# EEPROM.net
KiCad netlist of a schematic drawn in Altium Designer
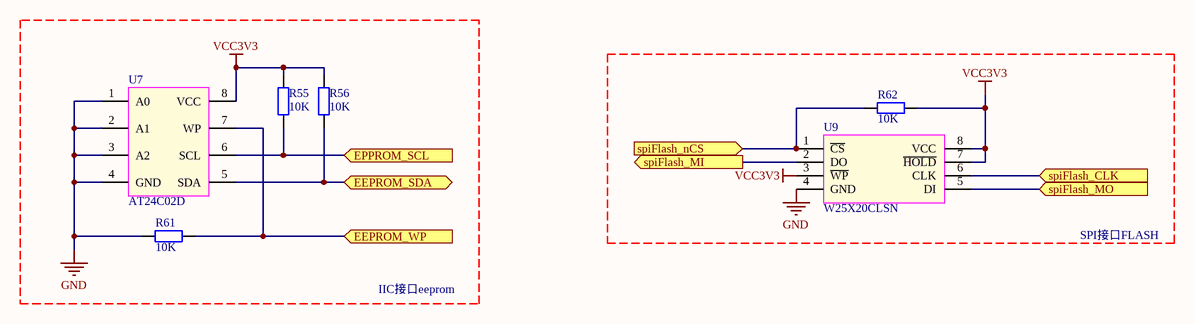
[diagram p0: EEPROM.SchDoc]

(export (version "E")
  (design (tool "Eeschema 10.0.6"))
  (components
    (comp (ref "R55")
      (value "10K")
      (footprint "R0603")
      (libsource (lib "altium-import") (part "root_3_RES_06_"))
    )
    (comp (ref "R56")
      (value "10K")
      (footprint "R0603")
      (libsource (lib "altium-import") (part "root_3_RES_06_"))
    )
    (comp (ref "R61")
      (value "10K")
      (footprint "R0603")
      (libsource (lib "altium-import") (part "root_0_RES_06_"))
    )
    (comp (ref "R62")
      (value "10K")
      (footprint "R0603")
      (libsource (lib "altium-import") (part "root_0_RES_06_"))
    )
    (comp (ref "U7")
      (value "AT24C02D")
      (footprint "SOP8")
      (description "EEPROM")
      (libsource (lib "MAX51") (part "AT24C02D"))
    )
    (comp (ref "U9")
      (value "W25X20CLSN")
      (footprint "SOP8")
      (description "2M-bit/256K Byte(262,144)")
      (libsource (lib "MAX51") (part "W25X20CLSN"))
    )
  )
  (nets
    (net (code "1") (name "/EEPROM_SDA") (class "Default")
      (node (ref "R56") (pin "2") (pinfunction "2_2") (pintype "passive"))
      (node (ref "U7") (pin "5") (pinfunction "SDA_5") (pintype "passive"))
    )
    (net (code "2") (name "/EEPROM_WP") (class "Default")
      (node (ref "R61") (pin "2") (pinfunction "2_2") (pintype "passive"))
      (node (ref "U7") (pin "7") (pinfunction "WP_7") (pintype "passive"))
    )
    (net (code "3") (name "/EPPROM_SCL") (class "Default")
      (node (ref "R55") (pin "2") (pinfunction "2_2") (pintype "passive"))
      (node (ref "U7") (pin "6") (pinfunction "SCL_6") (pintype "passive"))
    )
    (net (code "4") (name "/spiFlash_CLK") (class "Default")
      (node (ref "U9") (pin "6") (pinfunction "CLK_6") (pintype "passive"))
    )
    (net (code "5") (name "/spiFlash_MI") (class "Default")
      (node (ref "U9") (pin "2") (pinfunction "DO_2") (pintype "passive"))
    )
    (net (code "6") (name "/spiFlash_MO") (class "Default")
      (node (ref "U9") (pin "5") (pinfunction "DI_5") (pintype "passive"))
    )
    (net (code "7") (name "/spiFlash_nCS") (class "Default")
      (node (ref "R62") (pin "1") (pinfunction "1_1") (pintype "passive"))
      (node (ref "U9") (pin "1") (pinfunction "~{CS}_1") (pintype "passive"))
    )
    (net (code "8") (name "GND") (class "Default")
      (node (ref "R61") (pin "1") (pinfunction "1_1") (pintype "passive"))
      (node (ref "U7") (pin "1") (pinfunction "A0_1") (pintype "passive"))
      (node (ref "U7") (pin "2") (pinfunction "A1_2") (pintype "passive"))
      (node (ref "U7") (pin "3") (pinfunction "A2_3") (pintype "passive"))
      (node (ref "U7") (pin "4") (pinfunction "GND_4") (pintype "passive"))
      (node (ref "U9") (pin "4") (pinfunction "GND_4") (pintype "passive"))
    )
    (net (code "9") (name "VCC3V3") (class "Default")
      (node (ref "R55") (pin "1") (pinfunction "1_1") (pintype "passive"))
      (node (ref "R56") (pin "1") (pinfunction "1_1") (pintype "passive"))
      (node (ref "R62") (pin "2") (pinfunction "2_2") (pintype "passive"))
      (node (ref "U7") (pin "8") (pinfunction "VCC_8") (pintype "passive"))
      (node (ref "U9") (pin "3") (pinfunction "~{WP}_3") (pintype "passive"))
      (node (ref "U9") (pin "7") (pinfunction "~{HOLD}_7") (pintype "passive"))
      (node (ref "U9") (pin "8") (pinfunction "VCC_8") (pintype "passive"))
    )
  )
)
